# Shema.net
KiCad netlist of a schematic drawn in Altium Designer
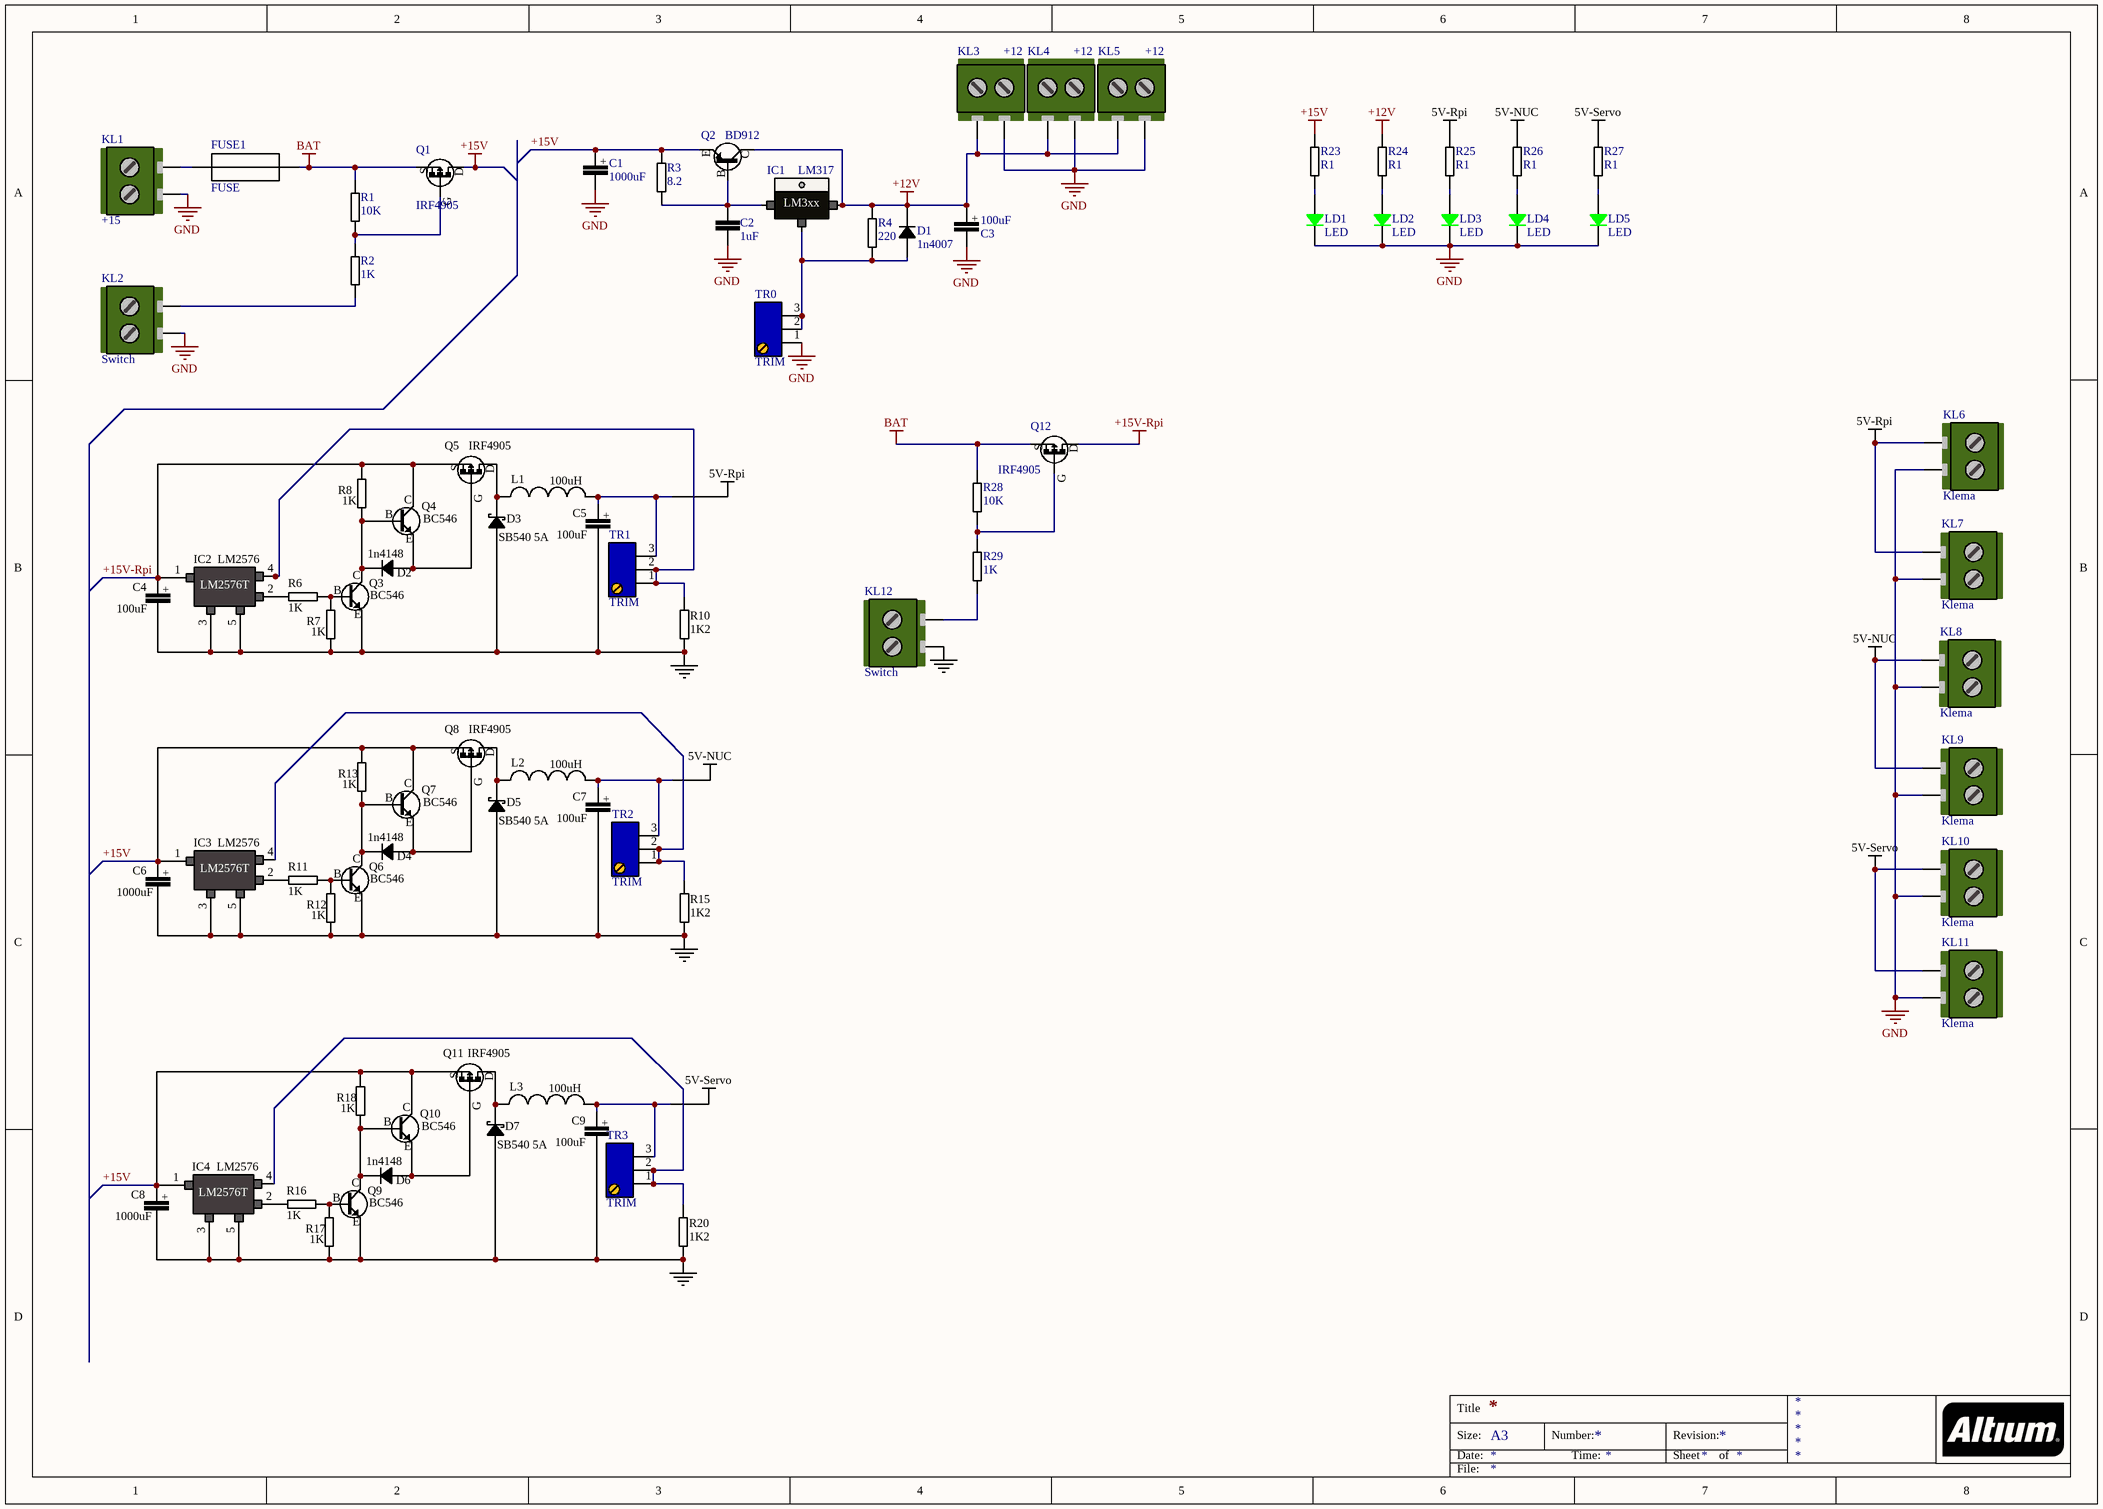
[diagram p0: Shema.SchDoc]

(export (version "E")
  (design (tool "Eeschema 10.0.6"))
  (components
    (comp (ref "100uF")
      (value "C3")
      (footprint "C2(elektrolit)")
      (libsource (lib "KILEX LIB SCH") (part "C2"))
    )
    (comp (ref "C1")
      (value "1000uF")
      (footprint "C2(elektrolit)")
      (libsource (lib "KILEX LIB SCH") (part "C2"))
    )
    (comp (ref "C2") (value "1uF") (footprint "C1(ceramic)") (libsource (lib "KILEX LIB SCH") (part "C1")))
    (comp (ref "C4")
      (value "100uF")
      (footprint "C2(elektrolit)")
      (libsource (lib "KILEX LIB SCH") (part "C2"))
    )
    (comp (ref "C5")
      (value "100uF")
      (footprint "C2(elektrolit)")
      (libsource (lib "KILEX LIB SCH") (part "C2"))
    )
    (comp (ref "C6")
      (value "1000uF")
      (footprint "C2(elektrolit)")
      (libsource (lib "KILEX LIB SCH") (part "C2"))
    )
    (comp (ref "C7")
      (value "100uF")
      (footprint "C2(elektrolit)")
      (libsource (lib "KILEX LIB SCH") (part "C2"))
    )
    (comp (ref "C8")
      (value "1000uF")
      (footprint "C2(elektrolit)")
      (libsource (lib "KILEX LIB SCH") (part "C2"))
    )
    (comp (ref "C9")
      (value "100uF")
      (footprint "C2(elektrolit)")
      (libsource (lib "KILEX LIB SCH") (part "C2"))
    )
    (comp (ref "D1")
      (value "1n4007")
      (footprint "D1(300milsa)")
      (libsource (lib "KILEX LIB SCH") (part "D1"))
    )
    (comp (ref "D2")
      (value "1n4148")
      (footprint "D1(300milsa)")
      (libsource (lib "KILEX LIB SCH") (part "D1"))
    )
    (comp (ref "D3")
      (value "SB540 5A")
      (footprint "D2(5A)")
      (libsource (lib "KILEX LIB SCH") (part "Sotki Diode"))
    )
    (comp (ref "D4")
      (value "1n4148")
      (footprint "D1(300milsa)")
      (libsource (lib "KILEX LIB SCH") (part "D1"))
    )
    (comp (ref "D5")
      (value "SB540 5A")
      (footprint "D2(5A)")
      (libsource (lib "KILEX LIB SCH") (part "Sotki Diode"))
    )
    (comp (ref "D6")
      (value "1n4148")
      (footprint "D1(300milsa)")
      (libsource (lib "KILEX LIB SCH") (part "D1"))
    )
    (comp (ref "D7")
      (value "SB540 5A")
      (footprint "D2(5A)")
      (libsource (lib "KILEX LIB SCH") (part "Sotki Diode"))
    )
    (comp (ref "FUSE1") (value "FUSE") (footprint "Osigurac") (libsource (lib "KILEX LIB SCH") (part "FUSE")))
    (comp (ref "IC1")
      (value "LM317")
      (footprint "TO220")
      (libsource (lib "KILEX LIB SCH") (part "LM317/LM350"))
    )
    (comp (ref "IC2") (value "LM2576") (footprint "LM2576") (libsource (lib "KILEX LIB SCH") (part "LM2576")))
    (comp (ref "IC3") (value "LM2576") (footprint "LM2576") (libsource (lib "KILEX LIB SCH") (part "LM2576")))
    (comp (ref "IC4") (value "LM2576") (footprint "LM2576") (libsource (lib "KILEX LIB SCH") (part "LM2576")))
    (comp (ref "KL1") (value "+15") (footprint "Klema") (libsource (lib "") (part "Klema_2")))
    (comp (ref "KL2") (value "Switch") (footprint "Klema") (libsource (lib "") (part "Klema_2")))
    (comp (ref "KL3") (value "+12") (footprint "Klema") (libsource (lib "KILEX LIB SCH") (part "Klema")))
    (comp (ref "KL4") (value "+12") (footprint "Klema") (libsource (lib "KILEX LIB SCH") (part "Klema")))
    (comp (ref "KL5") (value "+12") (footprint "Klema") (libsource (lib "KILEX LIB SCH") (part "Klema")))
    (comp (ref "KL6") (value "Klema") (footprint "Klema") (libsource (lib "") (part "Klema_1")))
    (comp (ref "KL7") (value "Klema") (footprint "Klema") (libsource (lib "") (part "Klema_1")))
    (comp (ref "KL8") (value "Klema") (footprint "Klema") (libsource (lib "") (part "Klema_1")))
    (comp (ref "KL9") (value "Klema") (footprint "Klema") (libsource (lib "") (part "Klema_1")))
    (comp (ref "KL10") (value "Klema") (footprint "Klema") (libsource (lib "") (part "Klema_1")))
    (comp (ref "KL11") (value "Klema") (footprint "Klema") (libsource (lib "") (part "Klema_1")))
    (comp (ref "KL12") (value "Switch") (footprint "Klema") (libsource (lib "") (part "Klema_2")))
    (comp (ref "L1")
      (value "100uH")
      (footprint "Coil(600mils)")
      (libsource (lib "KILEX LIB SCH") (part "Coil"))
    )
    (comp (ref "L2")
      (value "100uH")
      (footprint "Coil(600mils)")
      (libsource (lib "KILEX LIB SCH") (part "Coil"))
    )
    (comp (ref "L3")
      (value "100uH")
      (footprint "Coil(600mils)")
      (libsource (lib "KILEX LIB SCH") (part "Coil"))
    )
    (comp (ref "LD1") (value "LED") (footprint "LED(3mm)") (libsource (lib "KILEX LIB SCH") (part "LED")))
    (comp (ref "LD2") (value "LED") (footprint "LED(3mm)") (libsource (lib "KILEX LIB SCH") (part "LED")))
    (comp (ref "LD3") (value "LED") (footprint "LED(3mm)") (libsource (lib "KILEX LIB SCH") (part "LED")))
    (comp (ref "LD4") (value "LED") (footprint "LED(3mm)") (libsource (lib "KILEX LIB SCH") (part "LED")))
    (comp (ref "LD5") (value "LED") (footprint "LED(3mm)") (libsource (lib "KILEX LIB SCH") (part "LED")))
    (comp (ref "Q1")
      (value "IRF4905")
      (footprint "TO220")
      (libsource (lib "KILEX LIB SCH") (part "P-Channel MOSFET"))
    )
    (comp (ref "Q2")
      (value "BD912")
      (footprint "TO220")
      (libsource (lib "KILEX LIB SCH") (part "Transistor PNP"))
    )
    (comp (ref "Q3")
      (value "BC546")
      (footprint "TO-92")
      (libsource (lib "KILEX LIB SCH") (part "Transistor NPN"))
    )
    (comp (ref "Q4")
      (value "BC546")
      (footprint "TO-92")
      (libsource (lib "KILEX LIB SCH") (part "Transistor NPN"))
    )
    (comp (ref "Q5")
      (value "IRF4905")
      (footprint "TO220")
      (libsource (lib "KILEX LIB SCH") (part "P-Channel MOSFET"))
    )
    (comp (ref "Q6")
      (value "BC546")
      (footprint "TO-92")
      (libsource (lib "KILEX LIB SCH") (part "Transistor NPN"))
    )
    (comp (ref "Q7")
      (value "BC546")
      (footprint "TO-92")
      (libsource (lib "KILEX LIB SCH") (part "Transistor NPN"))
    )
    (comp (ref "Q8")
      (value "IRF4905")
      (footprint "TO220")
      (libsource (lib "KILEX LIB SCH") (part "P-Channel MOSFET"))
    )
    (comp (ref "Q9")
      (value "BC546")
      (footprint "TO-92")
      (libsource (lib "KILEX LIB SCH") (part "Transistor NPN"))
    )
    (comp (ref "Q10")
      (value "BC546")
      (footprint "TO-92")
      (libsource (lib "KILEX LIB SCH") (part "Transistor NPN"))
    )
    (comp (ref "Q11")
      (value "IRF4905")
      (footprint "TO220")
      (libsource (lib "KILEX LIB SCH") (part "P-Channel MOSFET"))
    )
    (comp (ref "Q12")
      (value "IRF4905")
      (footprint "TO220")
      (libsource (lib "KILEX LIB SCH") (part "P-Channel MOSFET"))
    )
    (comp (ref "R1") (value "10K") (footprint "R1(300milsa)") (libsource (lib "KILEX LIB SCH") (part "R1")))
    (comp (ref "R2") (value "1K") (footprint "R1(300milsa)") (libsource (lib "KILEX LIB SCH") (part "R1")))
    (comp (ref "R3") (value "8.2") (footprint "R1(2W)") (libsource (lib "KILEX LIB SCH") (part "R1")))
    (comp (ref "R4") (value "220") (footprint "R1(300milsa)") (libsource (lib "KILEX LIB SCH") (part "R1")))
    (comp (ref "R6") (value "1K") (footprint "R1(300milsa)") (libsource (lib "KILEX LIB SCH") (part "R1")))
    (comp (ref "R7") (value "1K") (footprint "R1(300milsa)") (libsource (lib "KILEX LIB SCH") (part "R1")))
    (comp (ref "R8") (value "1K") (footprint "R1(300milsa)") (libsource (lib "KILEX LIB SCH") (part "R1")))
    (comp (ref "R10") (value "1K2") (footprint "R1(300milsa)") (libsource (lib "KILEX LIB SCH") (part "R1")))
    (comp (ref "R11") (value "1K") (footprint "R1(300milsa)") (libsource (lib "KILEX LIB SCH") (part "R1")))
    (comp (ref "R12") (value "1K") (footprint "R1(300milsa)") (libsource (lib "KILEX LIB SCH") (part "R1")))
    (comp (ref "R13") (value "1K") (footprint "R1(300milsa)") (libsource (lib "KILEX LIB SCH") (part "R1")))
    (comp (ref "R15") (value "1K2") (footprint "R1(300milsa)") (libsource (lib "KILEX LIB SCH") (part "R1")))
    (comp (ref "R16") (value "1K") (footprint "R1(300milsa)") (libsource (lib "KILEX LIB SCH") (part "R1")))
    (comp (ref "R17") (value "1K") (footprint "R1(300milsa)") (libsource (lib "KILEX LIB SCH") (part "R1")))
    (comp (ref "R18") (value "1K") (footprint "R1(300milsa)") (libsource (lib "KILEX LIB SCH") (part "R1")))
    (comp (ref "R20") (value "1K2") (footprint "R1(300milsa)") (libsource (lib "KILEX LIB SCH") (part "R1")))
    (comp (ref "R23") (value "R1") (footprint "R1(300milsa)") (libsource (lib "KILEX LIB SCH") (part "R1")))
    (comp (ref "R24") (value "R1") (footprint "R1(300milsa)") (libsource (lib "KILEX LIB SCH") (part "R1")))
    (comp (ref "R25") (value "R1") (footprint "R1(300milsa)") (libsource (lib "KILEX LIB SCH") (part "R1")))
    (comp (ref "R26") (value "R1") (footprint "R1(300milsa)") (libsource (lib "KILEX LIB SCH") (part "R1")))
    (comp (ref "R27") (value "R1") (footprint "R1(300milsa)") (libsource (lib "KILEX LIB SCH") (part "R1")))
    (comp (ref "R28") (value "10K") (footprint "R1(300milsa)") (libsource (lib "KILEX LIB SCH") (part "R1")))
    (comp (ref "R29") (value "1K") (footprint "R1(300milsa)") (libsource (lib "KILEX LIB SCH") (part "R1")))
    (comp (ref "TR0") (value "TRIM") (footprint "TRIM") (libsource (lib "KILEX LIB SCH") (part "TRIM")))
    (comp (ref "TR1") (value "TRIM") (footprint "TRIM") (libsource (lib "KILEX LIB SCH") (part "TRIM")))
    (comp (ref "TR2") (value "TRIM") (footprint "TRIM") (libsource (lib "KILEX LIB SCH") (part "TRIM")))
    (comp (ref "TR3") (value "TRIM") (footprint "TRIM") (libsource (lib "KILEX LIB SCH") (part "TRIM")))
  )
  (nets
    (net (code "1") (name "+12V") (class "Default")
      (node (ref "100uF") (pin "1") (pinfunction "1_1") (pintype "passive"))
      (node (ref "D1") (pin "2") (pinfunction "2_2") (pintype "passive"))
      (node (ref "IC1") (pin "2") (pinfunction "2_2") (pintype "passive"))
      (node (ref "KL3") (pin "1") (pinfunction "1_1") (pintype "passive"))
      (node (ref "KL4") (pin "1") (pinfunction "1_1") (pintype "passive"))
      (node (ref "KL5") (pin "1") (pinfunction "1_1") (pintype "passive"))
      (node (ref "Q2") (pin "3") (pinfunction "3_3") (pintype "passive"))
      (node (ref "R24") (pin "2") (pinfunction "2_2") (pintype "passive"))
      (node (ref "R4") (pin "2") (pinfunction "2_2") (pintype "passive"))
    )
    (net (code "2") (name "+15V") (class "Default")
      (node (ref "C1") (pin "1") (pinfunction "1_1") (pintype "passive"))
      (node (ref "C6") (pin "1") (pinfunction "1_1") (pintype "passive"))
      (node (ref "C8") (pin "1") (pinfunction "1_1") (pintype "passive"))
      (node (ref "IC3") (pin "1") (pinfunction "1_1") (pintype "passive"))
      (node (ref "IC4") (pin "1") (pinfunction "1_1") (pintype "passive"))
      (node (ref "Q1") (pin "2") (pinfunction "2_2") (pintype "passive"))
      (node (ref "Q10") (pin "2") (pinfunction "2_2") (pintype "passive"))
      (node (ref "Q11") (pin "3") (pinfunction "3_3") (pintype "passive"))
      (node (ref "Q2") (pin "2") (pinfunction "2_2") (pintype "passive"))
      (node (ref "Q7") (pin "2") (pinfunction "2_2") (pintype "passive"))
      (node (ref "Q8") (pin "3") (pinfunction "3_3") (pintype "passive"))
      (node (ref "R13") (pin "1") (pinfunction "1_1") (pintype "passive"))
      (node (ref "R18") (pin "1") (pinfunction "1_1") (pintype "passive"))
      (node (ref "R23") (pin "2") (pinfunction "2_2") (pintype "passive"))
      (node (ref "R3") (pin "2") (pinfunction "2_2") (pintype "passive"))
    )
    (net (code "3") (name "+15V-Rpi") (class "Default")
      (node (ref "C4") (pin "1") (pinfunction "1_1") (pintype "passive"))
      (node (ref "IC2") (pin "1") (pinfunction "1_1") (pintype "passive"))
      (node (ref "Q12") (pin "2") (pinfunction "2_2") (pintype "passive"))
      (node (ref "Q4") (pin "2") (pinfunction "2_2") (pintype "passive"))
      (node (ref "Q5") (pin "3") (pinfunction "3_3") (pintype "passive"))
      (node (ref "R8") (pin "1") (pinfunction "1_1") (pintype "passive"))
    )
    (net (code "4") (name "5V-NUC") (class "Default")
      (node (ref "C7") (pin "1") (pinfunction "1_1") (pintype "passive"))
      (node (ref "KL8") (pin "1") (pinfunction "1_1") (pintype "passive"))
      (node (ref "KL9") (pin "1") (pinfunction "1_1") (pintype "passive"))
      (node (ref "L2") (pin "2") (pintype "passive"))
      (node (ref "R26") (pin "2") (pinfunction "2_2") (pintype "passive"))
      (node (ref "TR2") (pin "3") (pinfunction "3_3") (pintype "passive"))
    )
    (net (code "5") (name "5V-Rpi") (class "Default")
      (node (ref "C5") (pin "1") (pinfunction "1_1") (pintype "passive"))
      (node (ref "KL6") (pin "1") (pinfunction "1_1") (pintype "passive"))
      (node (ref "KL7") (pin "1") (pinfunction "1_1") (pintype "passive"))
      (node (ref "L1") (pin "2") (pintype "passive"))
      (node (ref "R25") (pin "2") (pinfunction "2_2") (pintype "passive"))
      (node (ref "TR1") (pin "3") (pinfunction "3_3") (pintype "passive"))
    )
    (net (code "6") (name "5V-Servo") (class "Default")
      (node (ref "C9") (pin "1") (pinfunction "1_1") (pintype "passive"))
      (node (ref "KL10") (pin "1") (pinfunction "1_1") (pintype "passive"))
      (node (ref "KL11") (pin "1") (pinfunction "1_1") (pintype "passive"))
      (node (ref "L3") (pin "2") (pintype "passive"))
      (node (ref "R27") (pin "2") (pinfunction "2_2") (pintype "passive"))
      (node (ref "TR3") (pin "3") (pinfunction "3_3") (pintype "passive"))
    )
    (net (code "7") (name "BAT") (class "Default")
      (node (ref "FUSE1") (pin "2") (pinfunction "2_2") (pintype "passive"))
      (node (ref "Q1") (pin "3") (pinfunction "3_3") (pintype "passive"))
      (node (ref "Q12") (pin "3") (pinfunction "3_3") (pintype "passive"))
      (node (ref "R1") (pin "2") (pinfunction "2_2") (pintype "passive"))
      (node (ref "R28") (pin "2") (pinfunction "2_2") (pintype "passive"))
    )
    (net (code "8") (name "GND") (class "Default")
      (node (ref "100uF") (pin "2") (pinfunction "2_2") (pintype "passive"))
      (node (ref "C1") (pin "2") (pinfunction "2_2") (pintype "passive"))
      (node (ref "C2") (pin "1") (pinfunction "1_1") (pintype "passive"))
      (node (ref "C4") (pin "2") (pinfunction "2_2") (pintype "passive"))
      (node (ref "C5") (pin "2") (pinfunction "2_2") (pintype "passive"))
      (node (ref "C6") (pin "2") (pinfunction "2_2") (pintype "passive"))
      (node (ref "C7") (pin "2") (pinfunction "2_2") (pintype "passive"))
      (node (ref "C8") (pin "2") (pinfunction "2_2") (pintype "passive"))
      (node (ref "C9") (pin "2") (pinfunction "2_2") (pintype "passive"))
      (node (ref "D3") (pin "1") (pinfunction "1_1") (pintype "passive"))
      (node (ref "D5") (pin "1") (pinfunction "1_1") (pintype "passive"))
      (node (ref "D7") (pin "1") (pinfunction "1_1") (pintype "passive"))
      (node (ref "IC2") (pin "3") (pinfunction "3_3") (pintype "passive"))
      (node (ref "IC2") (pin "5") (pinfunction "5_5") (pintype "passive"))
      (node (ref "IC3") (pin "3") (pinfunction "3_3") (pintype "passive"))
      (node (ref "IC3") (pin "5") (pinfunction "5_5") (pintype "passive"))
      (node (ref "IC4") (pin "3") (pinfunction "3_3") (pintype "passive"))
      (node (ref "IC4") (pin "5") (pinfunction "5_5") (pintype "passive"))
      (node (ref "KL1") (pin "1") (pinfunction "1_1") (pintype "passive"))
      (node (ref "KL10") (pin "2") (pinfunction "2_2") (pintype "passive"))
      (node (ref "KL11") (pin "2") (pinfunction "2_2") (pintype "passive"))
      (node (ref "KL12") (pin "1") (pinfunction "1_1") (pintype "passive"))
      (node (ref "KL2") (pin "1") (pinfunction "1_1") (pintype "passive"))
      (node (ref "KL3") (pin "2") (pinfunction "2_2") (pintype "passive"))
      (node (ref "KL4") (pin "2") (pinfunction "2_2") (pintype "passive"))
      (node (ref "KL5") (pin "2") (pinfunction "2_2") (pintype "passive"))
      (node (ref "KL6") (pin "2") (pinfunction "2_2") (pintype "passive"))
      (node (ref "KL7") (pin "2") (pinfunction "2_2") (pintype "passive"))
      (node (ref "KL8") (pin "2") (pinfunction "2_2") (pintype "passive"))
      (node (ref "KL9") (pin "2") (pinfunction "2_2") (pintype "passive"))
      (node (ref "LD1") (pin "2") (pinfunction "2_2") (pintype "passive"))
      (node (ref "LD2") (pin "2") (pinfunction "2_2") (pintype "passive"))
      (node (ref "LD3") (pin "2") (pinfunction "2_2") (pintype "passive"))
      (node (ref "LD4") (pin "2") (pinfunction "2_2") (pintype "passive"))
      (node (ref "LD5") (pin "2") (pinfunction "2_2") (pintype "passive"))
      (node (ref "Q3") (pin "3") (pinfunction "3_3") (pintype "passive"))
      (node (ref "Q6") (pin "3") (pinfunction "3_3") (pintype "passive"))
      (node (ref "Q9") (pin "3") (pinfunction "3_3") (pintype "passive"))
      (node (ref "R10") (pin "2") (pinfunction "2_2") (pintype "passive"))
      (node (ref "R12") (pin "2") (pinfunction "2_2") (pintype "passive"))
      (node (ref "R15") (pin "2") (pinfunction "2_2") (pintype "passive"))
      (node (ref "R17") (pin "2") (pinfunction "2_2") (pintype "passive"))
      (node (ref "R20") (pin "2") (pinfunction "2_2") (pintype "passive"))
      (node (ref "R7") (pin "2") (pinfunction "2_2") (pintype "passive"))
      (node (ref "TR0") (pin "1") (pinfunction "1_1") (pintype "passive"))
    )
    (net (code "9") (name "Net-(C2-Pad2)") (class "Default")
      (node (ref "C2") (pin "2") (pinfunction "2_2") (pintype "passive"))
      (node (ref "IC1") (pin "3") (pinfunction "3_3") (pintype "passive"))
      (node (ref "Q2") (pin "1") (pinfunction "1_1") (pintype "passive"))
      (node (ref "R3") (pin "1") (pinfunction "1_1") (pintype "passive"))
    )
    (net (code "10") (name "Net-(D1-Pad1)") (class "Default")
      (node (ref "D1") (pin "1") (pinfunction "1_1") (pintype "passive"))
      (node (ref "IC1") (pin "1") (pinfunction "1_1") (pintype "passive"))
      (node (ref "R4") (pin "1") (pinfunction "1_1") (pintype "passive"))
      (node (ref "TR0") (pin "2") (pinfunction "2_2") (pintype "passive"))
      (node (ref "TR0") (pin "3") (pinfunction "3_3") (pintype "passive"))
    )
    (net (code "11") (name "Net-(D2-Pad1)") (class "Default")
      (node (ref "D2") (pin "1") (pinfunction "1_1") (pintype "passive"))
      (node (ref "Q4") (pin "3") (pinfunction "3_3") (pintype "passive"))
      (node (ref "Q5") (pin "1") (pinfunction "1_1") (pintype "passive"))
    )
    (net (code "12") (name "Net-(D2-Pad2)") (class "Default")
      (node (ref "D2") (pin "2") (pinfunction "2_2") (pintype "passive"))
      (node (ref "Q3") (pin "2") (pinfunction "2_2") (pintype "passive"))
      (node (ref "Q4") (pin "1") (pinfunction "1_1") (pintype "passive"))
      (node (ref "R8") (pin "2") (pinfunction "2_2") (pintype "passive"))
    )
    (net (code "13") (name "Net-(D3-Pad2)") (class "Default")
      (node (ref "D3") (pin "2") (pinfunction "2_2") (pintype "passive"))
      (node (ref "L1") (pin "1") (pinfunction "1_1") (pintype "passive"))
      (node (ref "Q5") (pin "2") (pinfunction "2_2") (pintype "passive"))
    )
    (net (code "14") (name "Net-(D4-Pad1)") (class "Default")
      (node (ref "D4") (pin "1") (pinfunction "1_1") (pintype "passive"))
      (node (ref "Q7") (pin "3") (pinfunction "3_3") (pintype "passive"))
      (node (ref "Q8") (pin "1") (pinfunction "1_1") (pintype "passive"))
    )
    (net (code "15") (name "Net-(D4-Pad2)") (class "Default")
      (node (ref "D4") (pin "2") (pinfunction "2_2") (pintype "passive"))
      (node (ref "Q6") (pin "2") (pinfunction "2_2") (pintype "passive"))
      (node (ref "Q7") (pin "1") (pinfunction "1_1") (pintype "passive"))
      (node (ref "R13") (pin "2") (pinfunction "2_2") (pintype "passive"))
    )
    (net (code "16") (name "Net-(D5-Pad2)") (class "Default")
      (node (ref "D5") (pin "2") (pinfunction "2_2") (pintype "passive"))
      (node (ref "L2") (pin "1") (pinfunction "1_1") (pintype "passive"))
      (node (ref "Q8") (pin "2") (pinfunction "2_2") (pintype "passive"))
    )
    (net (code "17") (name "Net-(D6-Pad1)") (class "Default")
      (node (ref "D6") (pin "1") (pinfunction "1_1") (pintype "passive"))
      (node (ref "Q10") (pin "3") (pinfunction "3_3") (pintype "passive"))
      (node (ref "Q11") (pin "1") (pinfunction "1_1") (pintype "passive"))
    )
    (net (code "18") (name "Net-(D6-Pad2)") (class "Default")
      (node (ref "D6") (pin "2") (pinfunction "2_2") (pintype "passive"))
      (node (ref "Q10") (pin "1") (pinfunction "1_1") (pintype "passive"))
      (node (ref "Q9") (pin "2") (pinfunction "2_2") (pintype "passive"))
      (node (ref "R18") (pin "2") (pinfunction "2_2") (pintype "passive"))
    )
    (net (code "19") (name "Net-(D7-Pad2)") (class "Default")
      (node (ref "D7") (pin "2") (pinfunction "2_2") (pintype "passive"))
      (node (ref "L3") (pin "1") (pinfunction "1_1") (pintype "passive"))
      (node (ref "Q11") (pin "2") (pinfunction "2_2") (pintype "passive"))
    )
    (net (code "20") (name "Net-(FUSE1-Pad1)") (class "Default")
      (node (ref "FUSE1") (pin "1") (pinfunction "1_1") (pintype "passive"))
      (node (ref "KL1") (pin "2") (pinfunction "2_2") (pintype "passive"))
    )
    (net (code "21") (name "Net-(IC2-Pad2)") (class "Default")
      (node (ref "IC2") (pin "2") (pinfunction "2_2") (pintype "passive"))
      (node (ref "R6") (pin "2") (pinfunction "2_2") (pintype "passive"))
    )
    (net (code "22") (name "Net-(IC2-Pad4)") (class "Default")
      (node (ref "IC2") (pin "4") (pinfunction "4_4") (pintype "passive"))
      (node (ref "R10") (pin "1") (pinfunction "1_1") (pintype "passive"))
      (node (ref "TR1") (pin "1") (pinfunction "1_1") (pintype "passive"))
      (node (ref "TR1") (pin "2") (pinfunction "2_2") (pintype "passive"))
    )
    (net (code "23") (name "Net-(IC3-Pad2)") (class "Default")
      (node (ref "IC3") (pin "2") (pinfunction "2_2") (pintype "passive"))
      (node (ref "R11") (pin "2") (pinfunction "2_2") (pintype "passive"))
    )
    (net (code "24") (name "Net-(IC3-Pad4)") (class "Default")
      (node (ref "IC3") (pin "4") (pinfunction "4_4") (pintype "passive"))
      (node (ref "R15") (pin "1") (pinfunction "1_1") (pintype "passive"))
      (node (ref "TR2") (pin "1") (pinfunction "1_1") (pintype "passive"))
      (node (ref "TR2") (pin "2") (pinfunction "2_2") (pintype "passive"))
    )
    (net (code "25") (name "Net-(IC4-Pad2)") (class "Default")
      (node (ref "IC4") (pin "2") (pinfunction "2_2") (pintype "passive"))
      (node (ref "R16") (pin "2") (pinfunction "2_2") (pintype "passive"))
    )
    (net (code "26") (name "Net-(IC4-Pad4)") (class "Default")
      (node (ref "IC4") (pin "4") (pinfunction "4_4") (pintype "passive"))
      (node (ref "R20") (pin "1") (pinfunction "1_1") (pintype "passive"))
      (node (ref "TR3") (pin "1") (pinfunction "1_1") (pintype "passive"))
      (node (ref "TR3") (pin "2") (pinfunction "2_2") (pintype "passive"))
    )
    (net (code "27") (name "Net-(KL2-Pad2)") (class "Default")
      (node (ref "KL2") (pin "2") (pinfunction "2_2") (pintype "passive"))
      (node (ref "R2") (pin "1") (pinfunction "1_1") (pintype "passive"))
    )
    (net (code "28") (name "Net-(KL12-Pad2)") (class "Default")
      (node (ref "KL12") (pin "2") (pinfunction "2_2") (pintype "passive"))
      (node (ref "R29") (pin "1") (pinfunction "1_1") (pintype "passive"))
    )
    (net (code "29") (name "Net-(LD1-Pad1)") (class "Default")
      (node (ref "LD1") (pin "1") (pinfunction "1_1") (pintype "passive"))
      (node (ref "R23") (pin "1") (pinfunction "1_1") (pintype "passive"))
    )
    (net (code "30") (name "Net-(LD2-Pad1)") (class "Default")
      (node (ref "LD2") (pin "1") (pinfunction "1_1") (pintype "passive"))
      (node (ref "R24") (pin "1") (pinfunction "1_1") (pintype "passive"))
    )
    (net (code "31") (name "Net-(LD3-Pad1)") (class "Default")
      (node (ref "LD3") (pin "1") (pinfunction "1_1") (pintype "passive"))
      (node (ref "R25") (pin "1") (pinfunction "1_1") (pintype "passive"))
    )
    (net (code "32") (name "Net-(LD4-Pad1)") (class "Default")
      (node (ref "LD4") (pin "1") (pinfunction "1_1") (pintype "passive"))
      (node (ref "R26") (pin "1") (pinfunction "1_1") (pintype "passive"))
    )
    (net (code "33") (name "Net-(LD5-Pad1)") (class "Default")
      (node (ref "LD5") (pin "1") (pinfunction "1_1") (pintype "passive"))
      (node (ref "R27") (pin "1") (pinfunction "1_1") (pintype "passive"))
    )
    (net (code "34") (name "Net-(Q1-Pad1)") (class "Default")
      (node (ref "Q1") (pin "1") (pinfunction "1_1") (pintype "passive"))
      (node (ref "R1") (pin "1") (pinfunction "1_1") (pintype "passive"))
      (node (ref "R2") (pin "2") (pinfunction "2_2") (pintype "passive"))
    )
    (net (code "35") (name "Net-(Q3-Pad1)") (class "Default")
      (node (ref "Q3") (pin "1") (pinfunction "1_1") (pintype "passive"))
      (node (ref "R6") (pin "1") (pinfunction "1_1") (pintype "passive"))
      (node (ref "R7") (pin "1") (pinfunction "1_1") (pintype "passive"))
    )
    (net (code "36") (name "Net-(Q6-Pad1)") (class "Default")
      (node (ref "Q6") (pin "1") (pinfunction "1_1") (pintype "passive"))
      (node (ref "R11") (pin "1") (pinfunction "1_1") (pintype "passive"))
      (node (ref "R12") (pin "1") (pinfunction "1_1") (pintype "passive"))
    )
    (net (code "37") (name "Net-(Q9-Pad1)") (class "Default")
      (node (ref "Q9") (pin "1") (pinfunction "1_1") (pintype "passive"))
      (node (ref "R16") (pin "1") (pinfunction "1_1") (pintype "passive"))
      (node (ref "R17") (pin "1") (pinfunction "1_1") (pintype "passive"))
    )
    (net (code "38") (name "Net-(Q12-Pad1)") (class "Default")
      (node (ref "Q12") (pin "1") (pinfunction "1_1") (pintype "passive"))
      (node (ref "R28") (pin "1") (pinfunction "1_1") (pintype "passive"))
      (node (ref "R29") (pin "2") (pinfunction "2_2") (pintype "passive"))
    )
  )
)
